# Sheet1.net
KiCad netlist of a schematic drawn in Altium Designer
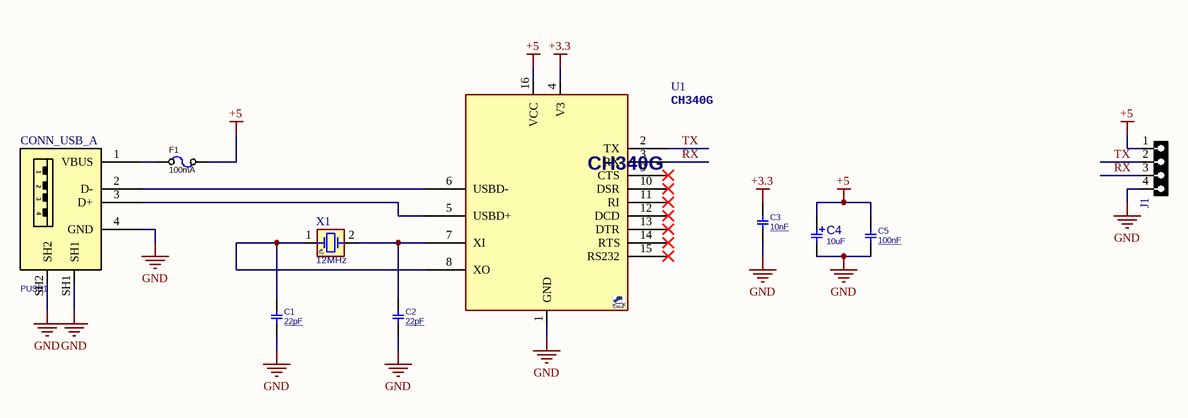
[diagram p0: Sheet1.SchDoc]

(export (version "E")
  (design (tool "Eeschema 10.0.6"))
  (components
    (comp (ref "C1")
      (value "22pF")
      (footprint "C1206")
      (description "CAP, FILM, 680nF, 16V, Acryl, 20%, 1206")
      (fields (field (name "MANF") "Murata"))
      (libsource (lib "Chila_PCB") (part "CAP_SMD_FILM"))
    )
    (comp (ref "C2")
      (value "22pF")
      (footprint "C1206")
      (description "CAP, FILM, 680nF, 16V, Acryl, 20%, 1206")
      (fields (field (name "MANF") "Murata"))
      (libsource (lib "Chila_PCB") (part "CAP_SMD_FILM"))
    )
    (comp (ref "C3")
      (value "10nF")
      (footprint "C1206")
      (description "CAP, FILM, 680nF, 16V, Acryl, 20%, 1206")
      (fields (field (name "MANF") "Murata"))
      (libsource (lib "Chila_PCB") (part "CAP_SMD_FILM"))
    )
    (comp (ref "C4")
      (value "10uF")
      (footprint "C_EL_5")
      (description "CAP, THD, ELEC,")
      (fields (field (name "MANF_P#") "MANF_PART#") (field (name "MANF") "MANF"))
      (libsource (lib "Chila_PCB") (part "CAP_SMD_EL"))
    )
    (comp (ref "C5")
      (value "100nF")
      (footprint "C1206")
      (description "CAP, FILM, 680nF, 16V, Acryl, 20%, 1206")
      (fields (field (name "MANF") "Murata"))
      (libsource (lib "Chila_PCB") (part "CAP_SMD_FILM"))
    )
    (comp (ref "F1")
      (value "100mA")
      (footprint "F1206")
      (description "Fuse, 3A, 32VDC, 1206, SMD, Slow Blow")
      (fields (field (name "MANF") "Bourns") (field (name "MANF_P#") "SF-1206SP300-2"))
      (libsource (lib "Chila_PCB") (part "FUSE_3A_1206_SLOW"))
    )
    (comp (ref "J1")
      (value "HDRF4")
      (footprint "HDR_F_1X4")
      (description "CONN, HEADER, Female, pitch: 2.54mm, 4POS")
      (libsource (lib "Chila_PCB") (part "HDR_F_1X4"))
    )
    (comp (ref "PUSB1")
      (value "CONN_USB_A")
      (footprint "USB_A_PLG_RA")
      (description "CONN, USB, A, PLUG, THD")
      (libsource (lib "Chila_PCB") (part "CONN_USB_A_PLUG"))
    )
    (comp (ref "U1")
      (value "CH340G")
      (footprint "SO_16")
      (description "USB-UART")
      (libsource (lib "Chila_PCB") (part "CH340G_SOP16"))
    )
    (comp (ref "X1")
      (value "12MHz")
      (footprint "XTL_2_11X5")
      (description "Crystal MOST POPULAR ABL HC49 PACKAGE")
      (fields (field (name "MANF") "ABRACON") (field (name "MANF_P#") "ABLS-8.000MHZ-B4-T"))
      (libsource (lib "Chila_PCB") (part "XTL_2_HC49_8MHz_SMD"))
    )
  )
  (nets
    (net (code "1") (name "+3.3") (class "Default")
      (node (ref "C3") (pin "2") (pinfunction "2_2") (pintype "passive"))
      (node (ref "U1") (pin "4") (pinfunction "V3_4") (pintype "passive"))
    )
    (net (code "2") (name "+5") (class "Default")
      (node (ref "C4") (pin "1") (pinfunction "1_1") (pintype "passive"))
      (node (ref "C5") (pin "2") (pinfunction "2_2") (pintype "passive"))
      (node (ref "F1") (pin "2") (pinfunction "2_2") (pintype "passive"))
      (node (ref "J1") (pin "1") (pinfunction "1_1") (pintype "passive"))
      (node (ref "U1") (pin "16") (pinfunction "VCC_16") (pintype "passive"))
    )
    (net (code "3") (name "/RX") (class "Default")
      (node (ref "J1") (pin "3") (pinfunction "3_3") (pintype "passive"))
      (node (ref "U1") (pin "3") (pinfunction "RX_3") (pintype "passive"))
    )
    (net (code "4") (name "/TX") (class "Default")
      (node (ref "J1") (pin "2") (pinfunction "2_2") (pintype "passive"))
      (node (ref "U1") (pin "2") (pinfunction "TX_2") (pintype "passive"))
    )
    (net (code "5") (name "GND") (class "Default")
      (node (ref "C1") (pin "1") (pinfunction "1_1") (pintype "passive"))
      (node (ref "C2") (pin "1") (pinfunction "1_1") (pintype "passive"))
      (node (ref "C3") (pin "1") (pinfunction "1_1") (pintype "passive"))
      (node (ref "C4") (pin "2") (pinfunction "2_2") (pintype "passive"))
      (node (ref "C5") (pin "1") (pinfunction "1_1") (pintype "passive"))
      (node (ref "J1") (pin "4") (pinfunction "4_4") (pintype "passive"))
      (node (ref "PUSB1") (pin "4") (pinfunction "GND_4") (pintype "passive"))
      (node (ref "PUSB1") (pin "SH1") (pinfunction "SH1_SH1") (pintype "passive"))
      (node (ref "PUSB1") (pin "SH2") (pinfunction "SH2_SH2") (pintype "passive"))
      (node (ref "U1") (pin "1") (pinfunction "GND_1") (pintype "passive"))
    )
    (net (code "6") (name "Net-(PUSB1-D+)") (class "Default")
      (node (ref "PUSB1") (pin "3") (pinfunction "D+_3") (pintype "passive"))
      (node (ref "U1") (pin "5") (pinfunction "USBD+_5") (pintype "passive"))
    )
    (net (code "7") (name "Net-(PUSB1-D-)") (class "Default")
      (node (ref "PUSB1") (pin "2") (pinfunction "D-_2") (pintype "passive"))
      (node (ref "U1") (pin "6") (pinfunction "USBD-_6") (pintype "passive"))
    )
    (net (code "8") (name "Net-(PUSB1-VBUS)") (class "Default")
      (node (ref "F1") (pin "1") (pinfunction "1_1") (pintype "passive"))
      (node (ref "PUSB1") (pin "1") (pinfunction "VBUS_1") (pintype "passive"))
    )
    (net (code "9") (name "Net-(U1-XI)") (class "Default")
      (node (ref "C2") (pin "2") (pinfunction "2_2") (pintype "passive"))
      (node (ref "U1") (pin "7") (pinfunction "XI_7") (pintype "passive"))
      (node (ref "X1") (pin "2") (pinfunction "OSC2_2") (pintype "passive"))
    )
    (net (code "10") (name "Net-(U1-XO)") (class "Default")
      (node (ref "C1") (pin "2") (pinfunction "2_2") (pintype "passive"))
      (node (ref "U1") (pin "8") (pinfunction "XO_8") (pintype "passive"))
      (node (ref "X1") (pin "1") (pinfunction "OSC1_1") (pintype "passive"))
    )
    (net (code "11") (name "unconnected-(U1-CTS-Pad9)") (class "Default")
      (node (ref "U1") (pin "9") (pinfunction "CTS_9") (pintype "passive+no_connect"))
    )
    (net (code "12") (name "unconnected-(U1-DCD-Pad12)") (class "Default")
      (node (ref "U1") (pin "12") (pinfunction "DCD_12") (pintype "passive+no_connect"))
    )
    (net (code "13") (name "unconnected-(U1-DSR-Pad10)") (class "Default")
      (node (ref "U1") (pin "10") (pinfunction "DSR_10") (pintype "passive+no_connect"))
    )
    (net (code "14") (name "unconnected-(U1-DTR-Pad13)") (class "Default")
      (node (ref "U1") (pin "13") (pinfunction "DTR_13") (pintype "passive+no_connect"))
    )
    (net (code "15") (name "unconnected-(U1-RI-Pad11)") (class "Default")
      (node (ref "U1") (pin "11") (pinfunction "RI_11") (pintype "passive+no_connect"))
    )
    (net (code "16") (name "unconnected-(U1-RS232-Pad15)") (class "Default")
      (node (ref "U1") (pin "15") (pinfunction "RS232_15") (pintype "passive+no_connect"))
    )
    (net (code "17") (name "unconnected-(U1-RTS-Pad14)") (class "Default")
      (node (ref "U1") (pin "14") (pinfunction "RTS_14") (pintype "passive+no_connect"))
    )
  )
)
